# OrmerodController.net
KiCad netlist of a schematic drawn in EAGLE
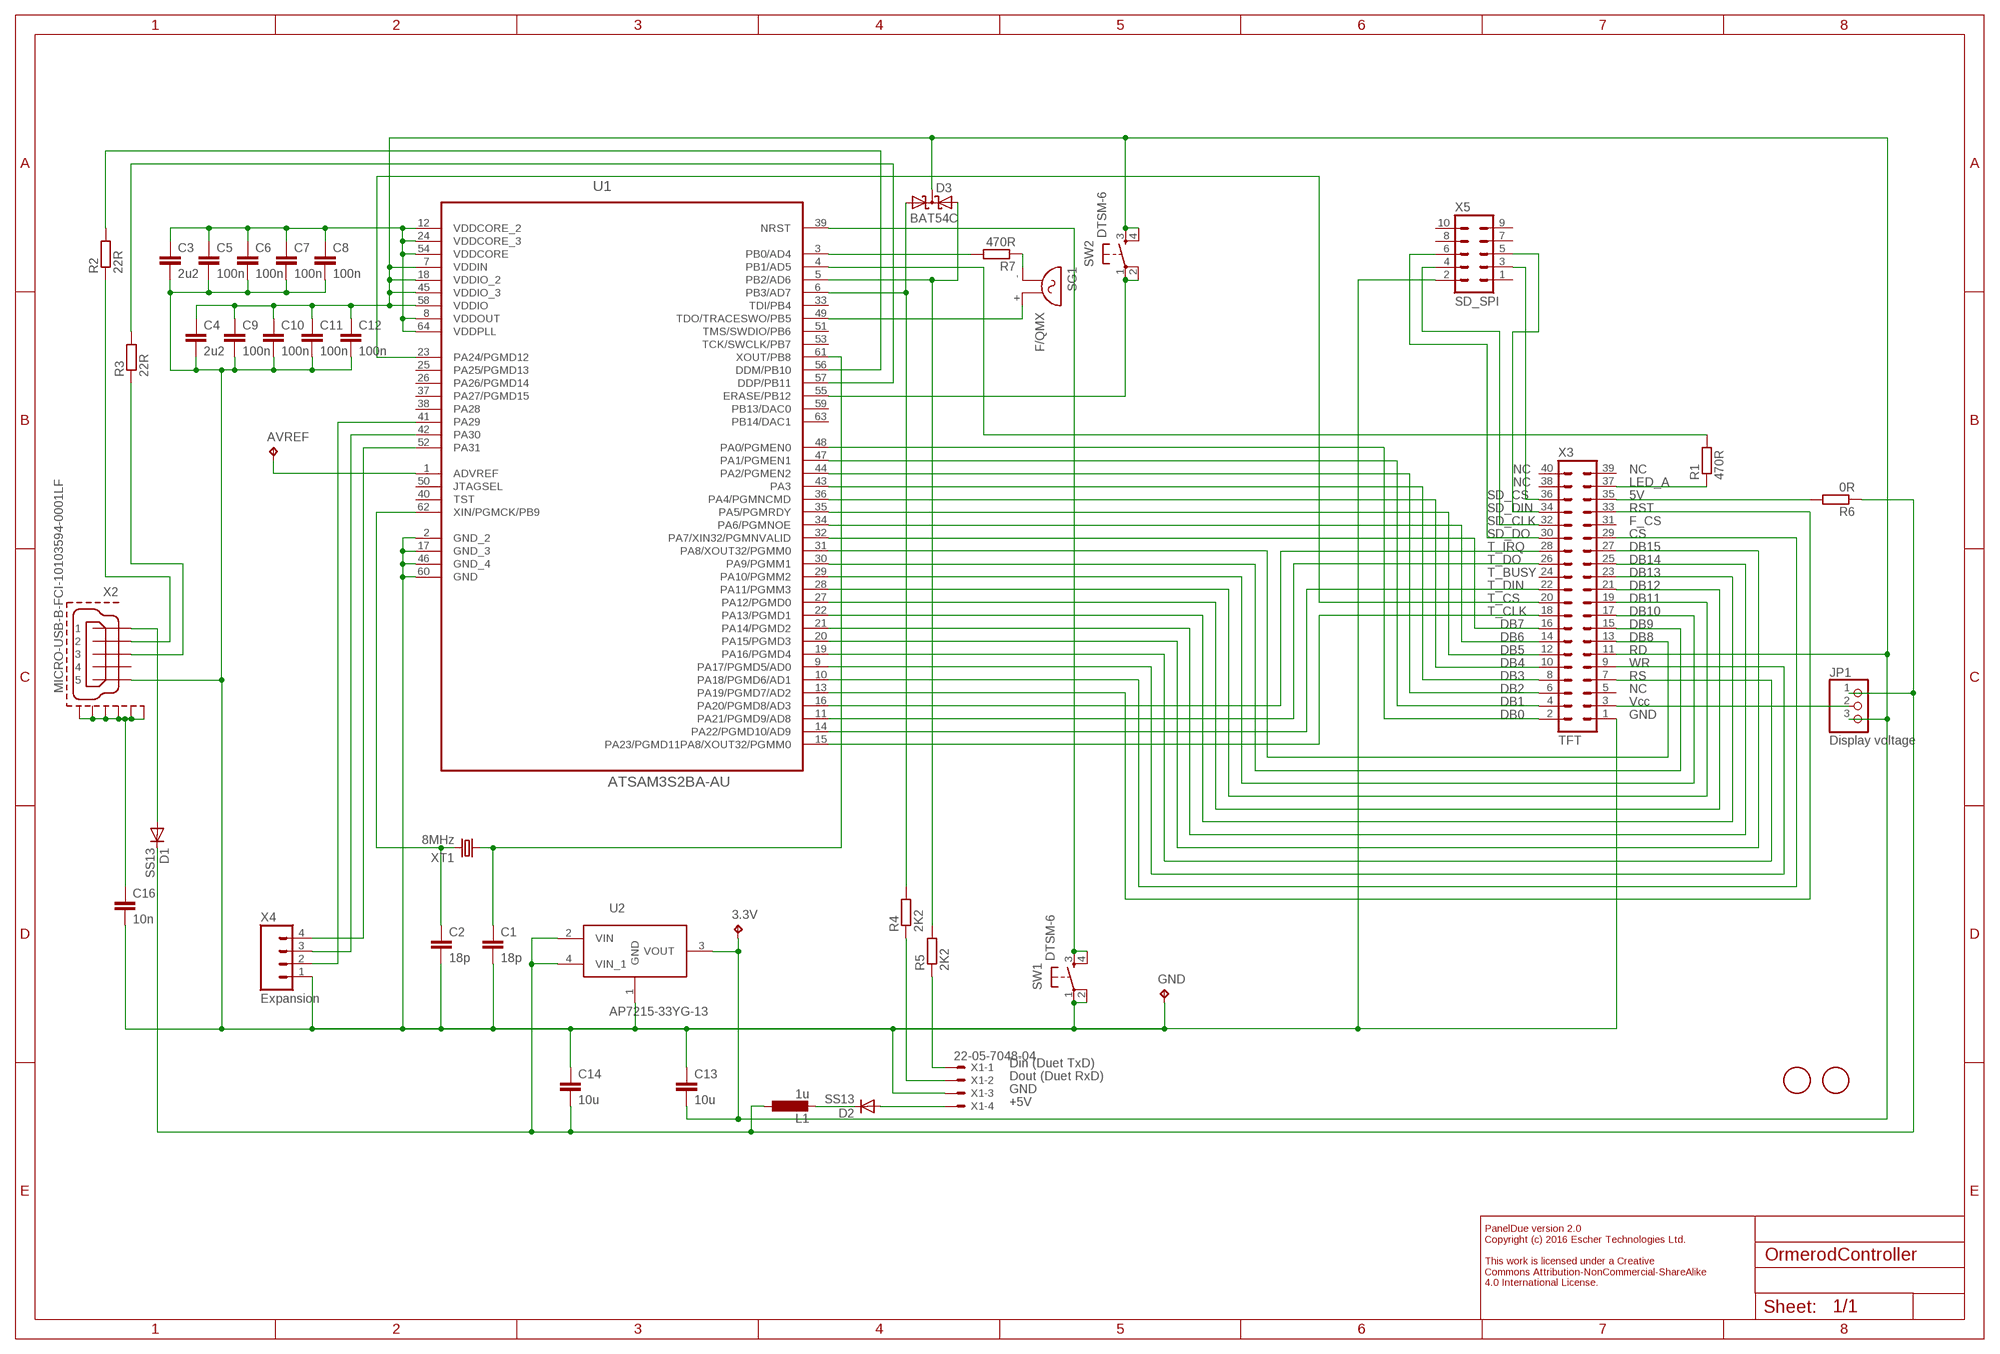
[diagram p0: schematic, sheet 1]

(export (version "E")
  (design (tool "Eeschema 10.0.6"))
  (components
    (comp (ref "3.3V")
      (value "TPPAD1-10")
      (footprint "eagle-import:P1-10")
      (libsource (lib "eagle-import") (part "TPPAD1-10"))
    )
    (comp (ref "AVREF")
      (value "TPPAD1-10")
      (footprint "eagle-import:P1-10")
      (libsource (lib "eagle-import") (part "TPPAD1-10"))
    )
    (comp (ref "C1")
      (value "18p")
      (footprint "eagle-import:C0603")
      (libsource (lib "eagle-import") (part "C-EUC0603"))
    )
    (comp (ref "C2")
      (value "18p")
      (footprint "eagle-import:C0603")
      (libsource (lib "eagle-import") (part "C-EUC0603"))
    )
    (comp (ref "C3")
      (value "2u2")
      (footprint "eagle-import:C0603")
      (libsource (lib "eagle-import") (part "C-EUC0603"))
    )
    (comp (ref "C4")
      (value "2u2")
      (footprint "eagle-import:C0603")
      (libsource (lib "eagle-import") (part "C-EUC0603"))
    )
    (comp (ref "C5")
      (value "100n")
      (footprint "eagle-import:C0603")
      (libsource (lib "eagle-import") (part "C-EUC0603"))
    )
    (comp (ref "C6")
      (value "100n")
      (footprint "eagle-import:C0603")
      (libsource (lib "eagle-import") (part "C-EUC0603"))
    )
    (comp (ref "C7")
      (value "100n")
      (footprint "eagle-import:C0603")
      (libsource (lib "eagle-import") (part "C-EUC0603"))
    )
    (comp (ref "C8")
      (value "100n")
      (footprint "eagle-import:C0603")
      (libsource (lib "eagle-import") (part "C-EUC0603"))
    )
    (comp (ref "C9")
      (value "100n")
      (footprint "eagle-import:C0603")
      (libsource (lib "eagle-import") (part "C-EUC0603"))
    )
    (comp (ref "C10")
      (value "100n")
      (footprint "eagle-import:C0603")
      (libsource (lib "eagle-import") (part "C-EUC0603"))
    )
    (comp (ref "C11")
      (value "100n")
      (footprint "eagle-import:C0603")
      (libsource (lib "eagle-import") (part "C-EUC0603"))
    )
    (comp (ref "C12")
      (value "100n")
      (footprint "eagle-import:C0603")
      (libsource (lib "eagle-import") (part "C-EUC0603"))
    )
    (comp (ref "C13")
      (value "10u")
      (footprint "eagle-import:C0805")
      (libsource (lib "eagle-import") (part "C-EUC0805"))
    )
    (comp (ref "C14")
      (value "10u")
      (footprint "eagle-import:C0805")
      (libsource (lib "eagle-import") (part "C-EUC0805"))
    )
    (comp (ref "C16")
      (value "10n")
      (footprint "eagle-import:C0603")
      (libsource (lib "eagle-import") (part "C-EUC0603"))
    )
    (comp (ref "D1")
      (value "SS13")
      (footprint "eagle-import:DO214AC")
      (libsource (lib "eagle-import") (part "DIODE-DO214AC"))
    )
    (comp (ref "D2")
      (value "SS13")
      (footprint "eagle-import:DO214AC")
      (libsource (lib "eagle-import") (part "DIODE-DO214AC"))
    )
    (comp (ref "D3")
      (value "BAT54C")
      (footprint "eagle-import:SOT23")
      (libsource (lib "eagle-import") (part "BAT54C"))
    )
    (comp (ref "GND")
      (value "TPPAD1-10")
      (footprint "eagle-import:P1-10")
      (libsource (lib "eagle-import") (part "TPPAD1-10"))
    )
    (comp (ref "JP1")
      (value "Display voltage")
      (footprint "eagle-import:1X03")
      (libsource (lib "eagle-import") (part "PINHD-1X3"))
    )
    (comp (ref "L1")
      (value "1u")
      (footprint "eagle-import:L2012C")
      (libsource (lib "eagle-import") (part "L-EUL2012C"))
    )
    (comp (ref "R1")
      (value "470R")
      (footprint "eagle-import:R0603")
      (libsource (lib "eagle-import") (part "R-EU_R0603"))
    )
    (comp (ref "R2")
      (value "22R")
      (footprint "eagle-import:R0603")
      (libsource (lib "eagle-import") (part "R-EU_R0603"))
    )
    (comp (ref "R3")
      (value "22R")
      (footprint "eagle-import:R0603")
      (libsource (lib "eagle-import") (part "R-EU_R0603"))
    )
    (comp (ref "R4")
      (value "2K2")
      (footprint "eagle-import:R0603")
      (libsource (lib "eagle-import") (part "R-EU_R0603"))
    )
    (comp (ref "R5")
      (value "2K2")
      (footprint "eagle-import:R0603")
      (libsource (lib "eagle-import") (part "R-EU_R0603"))
    )
    (comp (ref "R6")
      (value "0R")
      (footprint "eagle-import:R0603")
      (libsource (lib "eagle-import") (part "R-EU_R0603"))
    )
    (comp (ref "R7")
      (value "470R")
      (footprint "eagle-import:R0603")
      (libsource (lib "eagle-import") (part "R-EU_R0603"))
    )
    (comp (ref "SG1")
      (value "F/QMX")
      (footprint "eagle-import:F_QMX")
      (libsource (lib "eagle-import") (part "F/QMX"))
    )
    (comp (ref "SW1")
      (value "DTSM-6")
      (footprint "eagle-import:DTSM-6")
      (libsource (lib "eagle-import") (part "DTSM-6"))
    )
    (comp (ref "SW2")
      (value "DTSM-6")
      (footprint "eagle-import:DTSM-6")
      (libsource (lib "eagle-import") (part "DTSM-6"))
    )
    (comp (ref "U$1")
      (value "FIDUCIAL")
      (footprint "eagle-import:FIDUCIAL_1MM")
      (libsource (lib "eagle-import") (part "FIDUCIAL"))
    )
    (comp (ref "U$2")
      (value "FIDUCIAL")
      (footprint "eagle-import:FIDUCIAL_1MM")
      (libsource (lib "eagle-import") (part "FIDUCIAL"))
    )
    (comp (ref "U1")
      (value "ATSAM3S2BA-AU")
      (footprint "eagle-import:QFP50P1200X1200X160-64N")
      (libsource (lib "eagle-import") (part "ATSAM3S2BA-AU"))
    )
    (comp (ref "U2")
      (value "AP7215-33YG-13")
      (footprint "eagle-import:SOT150P400X160-4N")
      (fields (field (name "MPN") "MCP1702T-3302E/MB"))
      (libsource (lib "eagle-import") (part "MCP17-MCP1702T-3302E/MB"))
    )
    (comp (ref "X1")
      (value "22-05-7048-04")
      (footprint "eagle-import:7395-04")
      (libsource (lib "eagle-import") (part "22-?-0405-7048"))
    )
    (comp (ref "X2")
      (value "MICRO-USB-B-FCI-10103594-0001LF")
      (footprint "eagle-import:10103594-0001LF")
      (libsource (lib "eagle-import") (part "MICRO-USB-B-FCI-10103594-0001LF"))
    )
    (comp (ref "X3")
      (value "TFT")
      (footprint "eagle-import:MA20-2")
      (libsource (lib "eagle-import") (part "MA20-2"))
    )
    (comp (ref "X4")
      (value "Expansion")
      (footprint "eagle-import:1X04")
      (libsource (lib "eagle-import") (part "M04PTH"))
    )
    (comp (ref "X5")
      (value "SD_SPI")
      (footprint "eagle-import:ML10L")
      (libsource (lib "eagle-import") (part "ML10L"))
    )
    (comp (ref "XT1")
      (value "8MHz")
      (footprint "eagle-import:HC49UP")
      (libsource (lib "eagle-import") (part "CRYSTALHC49UP"))
    )
  )
  (nets
    (net (code "1") (name "Net-(C16-Pad1)") (class "Default")
      (node (ref "C16") (pin "1") (pinfunction "1_1") (pintype "passive"))
      (node (ref "X2") (pin "GND1") (pinfunction "GND1_GND1") (pintype "bidirectional"))
      (node (ref "X2") (pin "GND2") (pinfunction "GND2_GND2") (pintype "bidirectional"))
      (node (ref "X2") (pin "GND3") (pinfunction "GND3_GND3") (pintype "bidirectional"))
      (node (ref "X2") (pin "GND4") (pinfunction "GND4_GND4") (pintype "bidirectional"))
      (node (ref "X2") (pin "GND5") (pinfunction "GND5_GND5") (pintype "bidirectional"))
      (node (ref "X2") (pin "GND6") (pinfunction "GND6_GND6") (pintype "bidirectional"))
    )
    (net (code "2") (name "Net-(D1-PadA)") (class "Default")
      (node (ref "D1") (pin "A") (pinfunction "A_A") (pintype "passive"))
      (node (ref "X2") (pin "1") (pinfunction "1_1") (pintype "input"))
    )
    (net (code "3") (name "Net-(D2-PadC)") (class "Default")
      (node (ref "D2") (pin "C") (pinfunction "C_C") (pintype "passive"))
      (node (ref "L1") (pin "2") (pinfunction "2_2") (pintype "passive"))
    )
    (net (code "4") (name "Net-(D3-A1)") (class "Default")
      (node (ref "D3") (pin "1") (pinfunction "A1_1") (pintype "passive"))
      (node (ref "R4") (pin "2") (pinfunction "2_2") (pintype "passive"))
      (node (ref "U1") (pin "6") (pinfunction "PB3/AD7_6") (pintype "bidirectional"))
    )
    (net (code "5") (name "Net-(D3-A2)") (class "Default")
      (node (ref "D3") (pin "2") (pinfunction "A2_2") (pintype "passive"))
      (node (ref "R5") (pin "2") (pinfunction "2_2") (pintype "passive"))
      (node (ref "U1") (pin "5") (pinfunction "PB2/AD6_5") (pintype "bidirectional"))
    )
    (net (code "6") (name "Net-(D3-CC)") (class "Default")
      (node (ref "3.3V") (pin "TP") (pinfunction "TP_TP") (pintype "input"))
      (node (ref "C10") (pin "1") (pinfunction "1_1") (pintype "passive"))
      (node (ref "C11") (pin "1") (pinfunction "1_1") (pintype "passive"))
      (node (ref "C12") (pin "1") (pinfunction "1_1") (pintype "passive"))
      (node (ref "C13") (pin "2") (pinfunction "2_2") (pintype "passive"))
      (node (ref "C4") (pin "1") (pinfunction "1_1") (pintype "passive"))
      (node (ref "C9") (pin "1") (pinfunction "1_1") (pintype "passive"))
      (node (ref "D3") (pin "3") (pinfunction "CC_3") (pintype "passive"))
      (node (ref "JP1") (pin "3") (pinfunction "3_3") (pintype "passive"))
      (node (ref "SW2") (pin "3") (pinfunction "3_3") (pintype "passive"))
      (node (ref "SW2") (pin "4") (pinfunction "4_4") (pintype "passive"))
      (node (ref "U1") (pin "18") (pinfunction "VDDIO_2_18") (pintype "power_in"))
      (node (ref "U1") (pin "45") (pinfunction "VDDIO_3_45") (pintype "power_in"))
      (node (ref "U1") (pin "58") (pinfunction "VDDIO_58") (pintype "power_in"))
      (node (ref "U1") (pin "7") (pinfunction "VDDIN_7") (pintype "power_in"))
      (node (ref "U2") (pin "3") (pinfunction "VOUT_3") (pintype "output"))
      (node (ref "X3") (pin "11") (pinfunction "11_11") (pintype "passive"))
    )
    (net (code "7") (name "Net-(JP1-Pad2)") (class "Default")
      (node (ref "JP1") (pin "2") (pinfunction "2_2") (pintype "passive"))
      (node (ref "X3") (pin "3") (pinfunction "3_3") (pintype "passive"))
    )
    (net (code "8") (name "Net-(R1-Pad1)") (class "Default")
      (node (ref "R1") (pin "1") (pinfunction "1_1") (pintype "passive"))
      (node (ref "X3") (pin "37") (pinfunction "37_37") (pintype "passive"))
    )
    (net (code "9") (name "Net-(R2-Pad1)") (class "Default")
      (node (ref "R2") (pin "1") (pinfunction "1_1") (pintype "passive"))
      (node (ref "X2") (pin "2") (pinfunction "2_2") (pintype "input"))
    )
    (net (code "10") (name "Net-(R3-Pad1)") (class "Default")
      (node (ref "R3") (pin "1") (pinfunction "1_1") (pintype "passive"))
      (node (ref "X2") (pin "3") (pinfunction "3_3") (pintype "input"))
    )
    (net (code "11") (name "Net-(R6-Pad2)") (class "Default")
      (node (ref "R6") (pin "2") (pinfunction "2_2") (pintype "passive"))
      (node (ref "X3") (pin "35") (pinfunction "35_35") (pintype "passive"))
    )
    (net (code "12") (name "Net-(SG1-1)") (class "Default")
      (node (ref "R7") (pin "1") (pinfunction "1_1") (pintype "passive"))
      (node (ref "SG1") (pin "-") (pinfunction "1_-") (pintype "passive"))
    )
    (net (code "13") (name "Net-(SG1-2)") (class "Default")
      (node (ref "SG1") (pin "+") (pinfunction "2_+") (pintype "passive"))
      (node (ref "U1") (pin "49") (pinfunction "TDO/TRACESWO/PB5_49") (pintype "bidirectional"))
    )
    (net (code "14") (name "Net-(U1-ADVREF)") (class "Default")
      (node (ref "AVREF") (pin "TP") (pinfunction "TP_TP") (pintype "input"))
      (node (ref "U1") (pin "1") (pinfunction "ADVREF_1") (pintype "input"))
    )
    (net (code "15") (name "Net-(U1-DDM{slash}PB10)") (class "Default")
      (node (ref "R2") (pin "2") (pinfunction "2_2") (pintype "passive"))
      (node (ref "U1") (pin "56") (pinfunction "DDM/PB10_56") (pintype "bidirectional"))
    )
    (net (code "16") (name "Net-(U1-DDP{slash}PB11)") (class "Default")
      (node (ref "R3") (pin "2") (pinfunction "2_2") (pintype "passive"))
      (node (ref "U1") (pin "57") (pinfunction "DDP/PB11_57") (pintype "bidirectional"))
    )
    (net (code "17") (name "Net-(U1-ERASE{slash}PB12)") (class "Default")
      (node (ref "SW2") (pin "1") (pinfunction "1_1") (pintype "passive"))
      (node (ref "SW2") (pin "2") (pinfunction "2_2") (pintype "passive"))
      (node (ref "U1") (pin "55") (pinfunction "ERASE/PB12_55") (pintype "bidirectional"))
    )
    (net (code "18") (name "Net-(U1-GND)") (class "Default")
      (node (ref "C1") (pin "2") (pinfunction "2_2") (pintype "passive"))
      (node (ref "C10") (pin "2") (pinfunction "2_2") (pintype "passive"))
      (node (ref "C11") (pin "2") (pinfunction "2_2") (pintype "passive"))
      (node (ref "C12") (pin "2") (pinfunction "2_2") (pintype "passive"))
      (node (ref "C13") (pin "1") (pinfunction "1_1") (pintype "passive"))
      (node (ref "C14") (pin "1") (pinfunction "1_1") (pintype "passive"))
      (node (ref "C16") (pin "2") (pinfunction "2_2") (pintype "passive"))
      (node (ref "C2") (pin "2") (pinfunction "2_2") (pintype "passive"))
      (node (ref "C3") (pin "2") (pinfunction "2_2") (pintype "passive"))
      (node (ref "C4") (pin "2") (pinfunction "2_2") (pintype "passive"))
      (node (ref "C5") (pin "2") (pinfunction "2_2") (pintype "passive"))
      (node (ref "C6") (pin "2") (pinfunction "2_2") (pintype "passive"))
      (node (ref "C7") (pin "2") (pinfunction "2_2") (pintype "passive"))
      (node (ref "C8") (pin "2") (pinfunction "2_2") (pintype "passive"))
      (node (ref "C9") (pin "2") (pinfunction "2_2") (pintype "passive"))
      (node (ref "GND") (pin "TP") (pinfunction "TP_TP") (pintype "input"))
      (node (ref "SW1") (pin "1") (pinfunction "1_1") (pintype "passive"))
      (node (ref "SW1") (pin "2") (pinfunction "2_2") (pintype "passive"))
      (node (ref "U1") (pin "17") (pinfunction "GND_3_17") (pintype "passive"))
      (node (ref "U1") (pin "2") (pinfunction "GND_2_2") (pintype "passive"))
      (node (ref "U1") (pin "46") (pinfunction "GND_4_46") (pintype "passive"))
      (node (ref "U1") (pin "60") (pinfunction "GND_60") (pintype "passive"))
      (node (ref "U2") (pin "1") (pinfunction "GND_1") (pintype "power_in"))
      (node (ref "X1") (pin "3") (pinfunction "S_3") (pintype "passive"))
      (node (ref "X2") (pin "5") (pinfunction "5_5") (pintype "input"))
      (node (ref "X3") (pin "1") (pinfunction "1_1") (pintype "passive"))
      (node (ref "X4") (pin "1") (pinfunction "1_1") (pintype "passive"))
      (node (ref "X5") (pin "2") (pinfunction "2_2") (pintype "passive"))
    )
    (net (code "19") (name "Net-(U1-NRST)") (class "Default")
      (node (ref "SW1") (pin "3") (pinfunction "3_3") (pintype "passive"))
      (node (ref "SW1") (pin "4") (pinfunction "4_4") (pintype "passive"))
      (node (ref "U1") (pin "39") (pinfunction "NRST_39") (pintype "bidirectional"))
    )
    (net (code "20") (name "Net-(U1-PA0{slash}PGMEN0)") (class "Default")
      (node (ref "U1") (pin "48") (pinfunction "PA0/PGMEN0_48") (pintype "bidirectional"))
      (node (ref "X3") (pin "2") (pinfunction "2_2") (pintype "passive"))
    )
    (net (code "21") (name "Net-(U1-PA1{slash}PGMEN1)") (class "Default")
      (node (ref "U1") (pin "47") (pinfunction "PA1/PGMEN1_47") (pintype "bidirectional"))
      (node (ref "X3") (pin "4") (pinfunction "4_4") (pintype "passive"))
    )
    (net (code "22") (name "Net-(U1-PA2{slash}PGMEN2)") (class "Default")
      (node (ref "U1") (pin "44") (pinfunction "PA2/PGMEN2_44") (pintype "bidirectional"))
      (node (ref "X3") (pin "6") (pinfunction "6_6") (pintype "passive"))
    )
    (net (code "23") (name "Net-(U1-PA3)") (class "Default")
      (node (ref "U1") (pin "43") (pinfunction "PA3_43") (pintype "bidirectional"))
      (node (ref "X3") (pin "8") (pinfunction "8_8") (pintype "passive"))
    )
    (net (code "24") (name "Net-(U1-PA4{slash}PGMNCMD)") (class "Default")
      (node (ref "U1") (pin "36") (pinfunction "PA4/PGMNCMD_36") (pintype "bidirectional"))
      (node (ref "X3") (pin "10") (pinfunction "10_10") (pintype "passive"))
    )
    (net (code "25") (name "Net-(U1-PA5{slash}PGMRDY)") (class "Default")
      (node (ref "U1") (pin "35") (pinfunction "PA5/PGMRDY_35") (pintype "bidirectional"))
      (node (ref "X3") (pin "12") (pinfunction "12_12") (pintype "passive"))
    )
    (net (code "26") (name "Net-(U1-PA6{slash}PGMNOE)") (class "Default")
      (node (ref "U1") (pin "34") (pinfunction "PA6/PGMNOE_34") (pintype "bidirectional"))
      (node (ref "X3") (pin "14") (pinfunction "14_14") (pintype "passive"))
    )
    (net (code "27") (name "Net-(U1-PA7{slash}XIN32{slash}PGMNVALID)") (class "Default")
      (node (ref "U1") (pin "32") (pinfunction "PA7/XIN32/PGMNVALID_32") (pintype "bidirectional"))
      (node (ref "X3") (pin "16") (pinfunction "16_16") (pintype "passive"))
    )
    (net (code "28") (name "Net-(U1-PA8{slash}XOUT32{slash}PGMM0)") (class "Default")
      (node (ref "U1") (pin "31") (pinfunction "PA8/XOUT32/PGMM0_31") (pintype "bidirectional"))
      (node (ref "X3") (pin "13") (pinfunction "13_13") (pintype "passive"))
    )
    (net (code "29") (name "Net-(U1-PA9{slash}PGMM1)") (class "Default")
      (node (ref "U1") (pin "30") (pinfunction "PA9/PGMM1_30") (pintype "bidirectional"))
      (node (ref "X3") (pin "15") (pinfunction "15_15") (pintype "passive"))
    )
    (net (code "30") (name "Net-(U1-PA10{slash}PGMM2)") (class "Default")
      (node (ref "U1") (pin "29") (pinfunction "PA10/PGMM2_29") (pintype "bidirectional"))
      (node (ref "X3") (pin "17") (pinfunction "17_17") (pintype "passive"))
    )
    (net (code "31") (name "Net-(U1-PA11{slash}PGMM3)") (class "Default")
      (node (ref "U1") (pin "28") (pinfunction "PA11/PGMM3_28") (pintype "bidirectional"))
      (node (ref "X3") (pin "19") (pinfunction "19_19") (pintype "passive"))
    )
    (net (code "32") (name "Net-(U1-PA12{slash}PGMD0)") (class "Default")
      (node (ref "U1") (pin "27") (pinfunction "PA12/PGMD0_27") (pintype "bidirectional"))
      (node (ref "X3") (pin "21") (pinfunction "21_21") (pintype "passive"))
    )
    (net (code "33") (name "Net-(U1-PA13{slash}PGMD1)") (class "Default")
      (node (ref "U1") (pin "22") (pinfunction "PA13/PGMD1_22") (pintype "bidirectional"))
      (node (ref "X3") (pin "23") (pinfunction "23_23") (pintype "passive"))
    )
    (net (code "34") (name "Net-(U1-PA14{slash}PGMD2)") (class "Default")
      (node (ref "U1") (pin "21") (pinfunction "PA14/PGMD2_21") (pintype "bidirectional"))
      (node (ref "X3") (pin "25") (pinfunction "25_25") (pintype "passive"))
    )
    (net (code "35") (name "Net-(U1-PA15{slash}PGMD3)") (class "Default")
      (node (ref "U1") (pin "20") (pinfunction "PA15/PGMD3_20") (pintype "bidirectional"))
      (node (ref "X3") (pin "27") (pinfunction "27_27") (pintype "passive"))
    )
    (net (code "36") (name "Net-(U1-PA16{slash}PGMD4)") (class "Default")
      (node (ref "U1") (pin "19") (pinfunction "PA16/PGMD4_19") (pintype "bidirectional"))
      (node (ref "X3") (pin "7") (pinfunction "7_7") (pintype "passive"))
    )
    (net (code "37") (name "Net-(U1-PA17{slash}PGMD5{slash}AD0)") (class "Default")
      (node (ref "U1") (pin "9") (pinfunction "PA17/PGMD5/AD0_9") (pintype "bidirectional"))
      (node (ref "X3") (pin "9") (pinfunction "9_9") (pintype "passive"))
    )
    (net (code "38") (name "Net-(U1-PA18{slash}PGMD6{slash}AD1)") (class "Default")
      (node (ref "U1") (pin "10") (pinfunction "PA18/PGMD6/AD1_10") (pintype "bidirectional"))
      (node (ref "X3") (pin "29") (pinfunction "29_29") (pintype "passive"))
    )
    (net (code "39") (name "Net-(U1-PA19{slash}PGMD7{slash}AD2)") (class "Default")
      (node (ref "U1") (pin "13") (pinfunction "PA19/PGMD7/AD2_13") (pintype "bidirectional"))
      (node (ref "X3") (pin "33") (pinfunction "33_33") (pintype "passive"))
    )
    (net (code "40") (name "Net-(U1-PA20{slash}PGMD8{slash}AD3)") (class "Default")
      (node (ref "U1") (pin "16") (pinfunction "PA20/PGMD8/AD3_16") (pintype "bidirectional"))
      (node (ref "X3") (pin "28") (pinfunction "28_28") (pintype "passive"))
    )
    (net (code "41") (name "Net-(U1-PA21{slash}PGMD9{slash}AD8)") (class "Default")
      (node (ref "U1") (pin "11") (pinfunction "PA21/PGMD9/AD8_11") (pintype "bidirectional"))
      (node (ref "X3") (pin "26") (pinfunction "26_26") (pintype "passive"))
    )
    (net (code "42") (name "Net-(U1-PA22{slash}PGMD10{slash}AD9)") (class "Default")
      (node (ref "U1") (pin "14") (pinfunction "PA22/PGMD10/AD9_14") (pintype "bidirectional"))
      (node (ref "X3") (pin "22") (pinfunction "22_22") (pintype "passive"))
    )
    (net (code "43") (name "Net-(U1-PA23{slash}PGMD11PA8{slash}XOUT32{slash}PGMM0)") (class "Default")
      (node (ref "U1") (pin "15") (pinfunction "PA23/PGMD11PA8/XOUT32/PGMM0_15") (pintype "bidirectional"))
      (node (ref "X3") (pin "18") (pinfunction "18_18") (pintype "passive"))
    )
    (net (code "44") (name "Net-(U1-PA24{slash}PGMD12)") (class "Default")
      (node (ref "U1") (pin "23") (pinfunction "PA24/PGMD12_23") (pintype "bidirectional"))
      (node (ref "X3") (pin "20") (pinfunction "20_20") (pintype "passive"))
    )
    (net (code "45") (name "Net-(U1-PA29)") (class "Default")
      (node (ref "U1") (pin "41") (pinfunction "PA29_41") (pintype "bidirectional"))
      (node (ref "X4") (pin "2") (pinfunction "2_2") (pintype "passive"))
    )
    (net (code "46") (name "Net-(U1-PA30)") (class "Default")
      (node (ref "U1") (pin "42") (pinfunction "PA30_42") (pintype "bidirectional"))
      (node (ref "X4") (pin "3") (pinfunction "3_3") (pintype "passive"))
    )
    (net (code "47") (name "Net-(U1-PA31)") (class "Default")
      (node (ref "U1") (pin "52") (pinfunction "PA31_52") (pintype "bidirectional"))
      (node (ref "X4") (pin "4") (pinfunction "4_4") (pintype "passive"))
    )
    (net (code "48") (name "Net-(U1-PB0{slash}AD4)") (class "Default")
      (node (ref "R7") (pin "2") (pinfunction "2_2") (pintype "passive"))
      (node (ref "U1") (pin "3") (pinfunction "PB0/AD4_3") (pintype "bidirectional"))
    )
    (net (code "49") (name "Net-(U1-PB1{slash}AD5)") (class "Default")
      (node (ref "R1") (pin "2") (pinfunction "2_2") (pintype "passive"))
      (node (ref "U1") (pin "4") (pinfunction "PB1/AD5_4") (pintype "bidirectional"))
    )
    (net (code "50") (name "Net-(U1-VDDCORE)") (class "Default")
      (node (ref "C3") (pin "1") (pinfunction "1_1") (pintype "passive"))
      (node (ref "C5") (pin "1") (pinfunction "1_1") (pintype "passive"))
      (node (ref "C6") (pin "1") (pinfunction "1_1") (pintype "passive"))
      (node (ref "C7") (pin "1") (pinfunction "1_1") (pintype "passive"))
      (node (ref "C8") (pin "1") (pinfunction "1_1") (pintype "passive"))
      (node (ref "U1") (pin "12") (pinfunction "VDDCORE_2_12") (pintype "power_in"))
      (node (ref "U1") (pin "24") (pinfunction "VDDCORE_3_24") (pintype "power_in"))
      (node (ref "U1") (pin "54") (pinfunction "VDDCORE_54") (pintype "power_in"))
      (node (ref "U1") (pin "64") (pinfunction "VDDPLL_64") (pintype "power_in"))
      (node (ref "U1") (pin "8") (pinfunction "VDDOUT_8") (pintype "power_in"))
    )
    (net (code "51") (name "Net-(U1-XIN{slash}PGMCK{slash}PB9)") (class "Default")
      (node (ref "C2") (pin "1") (pinfunction "1_1") (pintype "passive"))
      (node (ref "U1") (pin "62") (pinfunction "XIN/PGMCK/PB9_62") (pintype "input"))
      (node (ref "XT1") (pin "2") (pinfunction "2_2") (pintype "passive"))
    )
    (net (code "52") (name "Net-(U1-XOUT{slash}PB8)") (class "Default")
      (node (ref "C1") (pin "1") (pinfunction "1_1") (pintype "passive"))
      (node (ref "U1") (pin "61") (pinfunction "XOUT/PB8_61") (pintype "output"))
      (node (ref "XT1") (pin "1") (pinfunction "1_1") (pintype "passive"))
    )
    (net (code "53") (name "Net-(U2-VIN)") (class "Default")
      (node (ref "C14") (pin "2") (pinfunction "2_2") (pintype "passive"))
      (node (ref "D1") (pin "C") (pinfunction "C_C") (pintype "passive"))
      (node (ref "JP1") (pin "1") (pinfunction "1_1") (pintype "passive"))
      (node (ref "L1") (pin "1") (pinfunction "1_1") (pintype "passive"))
      (node (ref "R6") (pin "1") (pinfunction "1_1") (pintype "passive"))
      (node (ref "U2") (pin "2") (pinfunction "VIN_2") (pintype "input"))
      (node (ref "U2") (pin "4") (pinfunction "VIN_1_4") (pintype "input"))
    )
    (net (code "54") (name "Net-(X1A-S)") (class "Default")
      (node (ref "R5") (pin "1") (pinfunction "1_1") (pintype "passive"))
      (node (ref "X1") (pin "1") (pinfunction "S_1") (pintype "passive"))
    )
    (net (code "55") (name "Net-(X1B-S)") (class "Default")
      (node (ref "R4") (pin "1") (pinfunction "1_1") (pintype "passive"))
      (node (ref "X1") (pin "2") (pinfunction "S_2") (pintype "passive"))
    )
    (net (code "56") (name "Net-(X1D-S)") (class "Default")
      (node (ref "D2") (pin "A") (pinfunction "A_A") (pintype "passive"))
      (node (ref "X1") (pin "4") (pinfunction "S_4") (pintype "passive"))
    )
    (net (code "57") (name "Net-(X3-Pad30)") (class "Default")
      (node (ref "X3") (pin "30") (pinfunction "30_30") (pintype "passive"))
      (node (ref "X5") (pin "6") (pinfunction "6_6") (pintype "passive"))
    )
    (net (code "58") (name "Net-(X3-Pad32)") (class "Default")
      (node (ref "X3") (pin "32") (pinfunction "32_32") (pintype "passive"))
      (node (ref "X5") (pin "4") (pinfunction "4_4") (pintype "passive"))
    )
    (net (code "59") (name "Net-(X3-Pad34)") (class "Default")
      (node (ref "X3") (pin "34") (pinfunction "34_34") (pintype "passive"))
      (node (ref "X5") (pin "5") (pinfunction "5_5") (pintype "passive"))
    )
    (net (code "60") (name "Net-(X3-Pad36)") (class "Default")
      (node (ref "X3") (pin "36") (pinfunction "36_36") (pintype "passive"))
      (node (ref "X5") (pin "3") (pinfunction "3_3") (pintype "passive"))
    )
    (net (code "61") (name "unconnected-(U1-JTAGSEL-Pad50)") (class "Default")
      (node (ref "U1") (pin "50") (pinfunction "JTAGSEL_50") (pintype "input"))
    )
    (net (code "62") (name "unconnected-(U1-PA25{slash}PGMD13-Pad25)") (class "Default")
      (node (ref "U1") (pin "25") (pinfunction "PA25/PGMD13_25") (pintype "bidirectional"))
    )
    (net (code "63") (name "unconnected-(U1-PA26{slash}PGMD14-Pad26)") (class "Default")
      (node (ref "U1") (pin "26") (pinfunction "PA26/PGMD14_26") (pintype "bidirectional"))
    )
    (net (code "64") (name "unconnected-(U1-PA27{slash}PGMD15-Pad37)") (class "Default")
      (node (ref "U1") (pin "37") (pinfunction "PA27/PGMD15_37") (pintype "bidirectional"))
    )
    (net (code "65") (name "unconnected-(U1-PA28-Pad38)") (class "Default")
      (node (ref "U1") (pin "38") (pinfunction "PA28_38") (pintype "bidirectional"))
    )
    (net (code "66") (name "unconnected-(U1-PB13{slash}DAC0-Pad59)") (class "Default")
      (node (ref "U1") (pin "59") (pinfunction "PB13/DAC0_59") (pintype "bidirectional"))
    )
    (net (code "67") (name "unconnected-(U1-PB14{slash}DAC1-Pad63)") (class "Default")
      (node (ref "U1") (pin "63") (pinfunction "PB14/DAC1_63") (pintype "bidirectional"))
    )
    (net (code "68") (name "unconnected-(U1-TCK{slash}SWCLK{slash}PB7-Pad53)") (class "Default")
      (node (ref "U1") (pin "53") (pinfunction "TCK/SWCLK/PB7_53") (pintype "bidirectional"))
    )
    (net (code "69") (name "unconnected-(U1-TDI{slash}PB4-Pad33)") (class "Default")
      (node (ref "U1") (pin "33") (pinfunction "TDI/PB4_33") (pintype "bidirectional"))
    )
    (net (code "70") (name "unconnected-(U1-TMS{slash}SWDIO{slash}PB6-Pad51)") (class "Default")
      (node (ref "U1") (pin "51") (pinfunction "TMS/SWDIO/PB6_51") (pintype "bidirectional"))
    )
    (net (code "71") (name "unconnected-(U1-TST-Pad40)") (class "Default")
      (node (ref "U1") (pin "40") (pinfunction "TST_40") (pintype "input"))
    )
    (net (code "72") (name "unconnected-(X2-Pad4)") (class "Default")
      (node (ref "X2") (pin "4") (pinfunction "4_4") (pintype "input"))
    )
    (net (code "73") (name "unconnected-(X3-Pad5)") (class "Default")
      (node (ref "X3") (pin "5") (pinfunction "5_5") (pintype "passive"))
    )
    (net (code "74") (name "unconnected-(X3-Pad24)") (class "Default")
      (node (ref "X3") (pin "24") (pinfunction "24_24") (pintype "passive"))
    )
    (net (code "75") (name "unconnected-(X3-Pad31)") (class "Default")
      (node (ref "X3") (pin "31") (pinfunction "31_31") (pintype "passive"))
    )
    (net (code "76") (name "unconnected-(X3-Pad38)") (class "Default")
      (node (ref "X3") (pin "38") (pinfunction "38_38") (pintype "passive"))
    )
    (net (code "77") (name "unconnected-(X3-Pad39)") (class "Default")
      (node (ref "X3") (pin "39") (pinfunction "39_39") (pintype "passive"))
    )
    (net (code "78") (name "unconnected-(X3-Pad40)") (class "Default")
      (node (ref "X3") (pin "40") (pinfunction "40_40") (pintype "passive"))
    )
    (net (code "79") (name "unconnected-(X5-Pad1)") (class "Default")
      (node (ref "X5") (pin "1") (pinfunction "1_1") (pintype "passive"))
    )
    (net (code "80") (name "unconnected-(X5-Pad7)") (class "Default")
      (node (ref "X5") (pin "7") (pinfunction "7_7") (pintype "passive"))
    )
    (net (code "81") (name "unconnected-(X5-Pad8)") (class "Default")
      (node (ref "X5") (pin "8") (pinfunction "8_8") (pintype "passive"))
    )
    (net (code "82") (name "unconnected-(X5-Pad9)") (class "Default")
      (node (ref "X5") (pin "9") (pinfunction "9_9") (pintype "passive"))
    )
    (net (code "83") (name "unconnected-(X5-Pad10)") (class "Default")
      (node (ref "X5") (pin "10") (pinfunction "10_10") (pintype "passive"))
    )
  )
)
